# rev02_20.net
KiCad netlist of a schematic drawn in Altium Designer
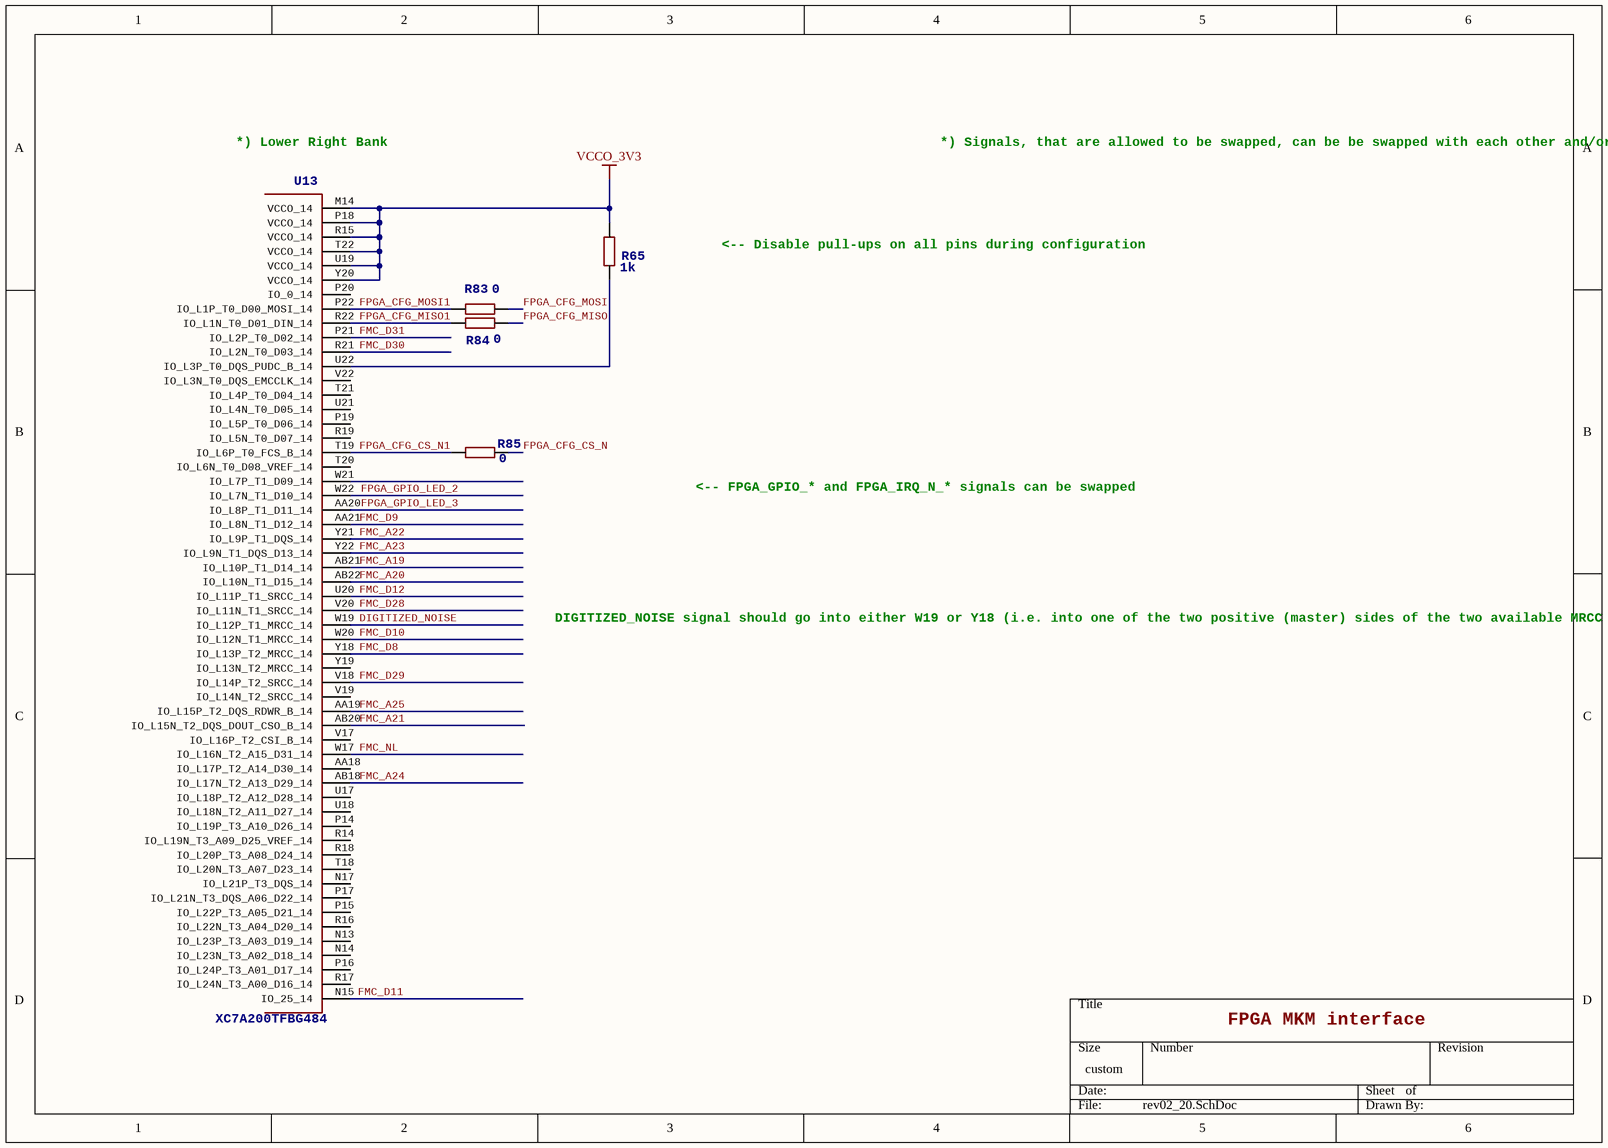
[diagram p0: rev02_20.SchDoc]

(export (version "E")
  (design (tool "Eeschema 10.0.6"))
  (components
    (comp (ref "R65")
      (value "1k")
      (footprint "R_0402")
      (description "0402 Resistor 5%")
      (fields (field (name "TOLERANCE") "5%") (field (name ">NAME") "R65"))
      (libsource (lib "resistor") (part "R-EU_R0402"))
    )
    (comp (ref "R83")
      (value "0")
      (footprint "R_0402")
      (description "0402 Resistor 5%")
      (libsource (lib "resistor") (part "R-EU_R0603"))
    )
    (comp (ref "R84")
      (value "0")
      (footprint "R_0402")
      (description "0402 Resistor 5%")
      (libsource (lib "resistor") (part "R-EU_R0603"))
    )
    (comp (ref "R85")
      (value "0")
      (footprint "R_0402")
      (description "0402 Resistor 5%")
      (libsource (lib "resistor") (part "R-EU_R0603"))
    )
    (comp (ref "U13")
      (value "XC7A200TFBG484")
      (footprint "BGA484C100P22X22_2300X2300X254")
      (description "Xilinx FPGA: XC7A200TFBG484")
      (fields
        (field (name "MFR") "Xilinx")
        (field (name "MPN") "XC7A200T-1FBG484C")
        (field (name ">NAME") "U13")
        (field (name ">VALUE") "XC7A200TFBG484")
      )
      (libsource (lib "Xilinx_XC7A200TFBG484") (part "XC7A200TFBG484"))
    )
  )
  (nets
    (net (code "1") (name "/DIGITIZED_NOISE") (class "Default")
      (node (ref "U13") (pin "W19") (pinfunction "IO_L12P_T1_MRCC_14_W19") (pintype "passive"))
    )
    (net (code "2") (name "/FMC_A19") (class "Default")
      (node (ref "U13") (pin "AB21") (pinfunction "IO_L10P_T1_D14_14_AB21") (pintype "passive"))
    )
    (net (code "3") (name "/FMC_A20") (class "Default")
      (node (ref "U13") (pin "AB22") (pinfunction "IO_L10N_T1_D15_14_AB22") (pintype "passive"))
    )
    (net (code "4") (name "/FMC_A21") (class "Default")
      (node (ref "U13") (pin "AB20") (pinfunction "IO_L15N_T2_DQS_DOUT_CSO_B_14_AB20") (pintype "passive"))
    )
    (net (code "5") (name "/FMC_A22") (class "Default")
      (node (ref "U13") (pin "Y21") (pinfunction "IO_L9P_T1_DQS_14_Y21") (pintype "passive"))
    )
    (net (code "6") (name "/FMC_A23") (class "Default")
      (node (ref "U13") (pin "Y22") (pinfunction "IO_L9N_T1_DQS_D13_14_Y22") (pintype "passive"))
    )
    (net (code "7") (name "/FMC_A24") (class "Default")
      (node (ref "U13") (pin "AB18") (pinfunction "IO_L17N_T2_A13_D29_14_AB18") (pintype "passive"))
    )
    (net (code "8") (name "/FMC_A25") (class "Default")
      (node (ref "U13") (pin "AA19") (pinfunction "IO_L15P_T2_DQS_RDWR_B_14_AA19") (pintype "passive"))
    )
    (net (code "9") (name "/FMC_D8") (class "Default")
      (node (ref "U13") (pin "Y18") (pinfunction "IO_L13P_T2_MRCC_14_Y18") (pintype "passive"))
    )
    (net (code "10") (name "/FMC_D9") (class "Default")
      (node (ref "U13") (pin "AA21") (pinfunction "IO_L8N_T1_D12_14_AA21") (pintype "passive"))
    )
    (net (code "11") (name "/FMC_D10") (class "Default")
      (node (ref "U13") (pin "W20") (pinfunction "IO_L12N_T1_MRCC_14_W20") (pintype "passive"))
    )
    (net (code "12") (name "/FMC_D11") (class "Default")
      (node (ref "U13") (pin "N15") (pinfunction "IO_25_14_N15") (pintype "passive"))
    )
    (net (code "13") (name "/FMC_D12") (class "Default")
      (node (ref "U13") (pin "U20") (pinfunction "IO_L11P_T1_SRCC_14_U20") (pintype "passive"))
    )
    (net (code "14") (name "/FMC_D28") (class "Default")
      (node (ref "U13") (pin "V20") (pinfunction "IO_L11N_T1_SRCC_14_V20") (pintype "passive"))
    )
    (net (code "15") (name "/FMC_D29") (class "Default")
      (node (ref "U13") (pin "V18") (pinfunction "IO_L14P_T2_SRCC_14_V18") (pintype "passive"))
    )
    (net (code "16") (name "/FMC_D30") (class "Default")
      (node (ref "U13") (pin "R21") (pinfunction "IO_L2N_T0_D03_14_R21") (pintype "passive"))
    )
    (net (code "17") (name "/FMC_D31") (class "Default")
      (node (ref "U13") (pin "P21") (pinfunction "IO_L2P_T0_D02_14_P21") (pintype "passive"))
    )
    (net (code "18") (name "/FMC_NL") (class "Default")
      (node (ref "U13") (pin "W17") (pinfunction "IO_L16N_T2_A15_D31_14_W17") (pintype "passive"))
    )
    (net (code "19") (name "/FPGA_CFG_CS_N") (class "Default")
      (node (ref "R85") (pin "1") (pinfunction "1_1") (pintype "passive"))
    )
    (net (code "20") (name "/FPGA_CFG_CS_N1") (class "Default")
      (node (ref "R85") (pin "2") (pinfunction "2_2") (pintype "passive"))
      (node (ref "U13") (pin "T19") (pinfunction "IO_L6P_T0_FCS_B_14_T19") (pintype "passive"))
    )
    (net (code "21") (name "/FPGA_CFG_MISO") (class "Default")
      (node (ref "R84") (pin "1") (pinfunction "1_1") (pintype "passive"))
    )
    (net (code "22") (name "/FPGA_CFG_MISO1") (class "Default")
      (node (ref "R84") (pin "2") (pinfunction "2_2") (pintype "passive"))
      (node (ref "U13") (pin "R22") (pinfunction "IO_L1N_T0_D01_DIN_14_R22") (pintype "passive"))
    )
    (net (code "23") (name "/FPGA_CFG_MOSI") (class "Default")
      (node (ref "R83") (pin "1") (pinfunction "1_1") (pintype "passive"))
    )
    (net (code "24") (name "/FPGA_CFG_MOSI1") (class "Default")
      (node (ref "R83") (pin "2") (pinfunction "2_2") (pintype "passive"))
      (node (ref "U13") (pin "P22") (pinfunction "IO_L1P_T0_D00_MOSI_14_P22") (pintype "passive"))
    )
    (net (code "25") (name "/FPGA_GPIO_LED_2") (class "Default")
      (node (ref "U13") (pin "W22") (pinfunction "IO_L7N_T1_D10_14_W22") (pintype "passive"))
    )
    (net (code "26") (name "/FPGA_GPIO_LED_3") (class "Default")
      (node (ref "U13") (pin "AA20") (pinfunction "IO_L8P_T1_D11_14_AA20") (pintype "passive"))
    )
    (net (code "27") (name "Net-(U13C-IO_L3P_T0_DQS_PUDC_B_14)") (class "Default")
      (node (ref "R65") (pin "1") (pinfunction "1_1") (pintype "passive"))
      (node (ref "U13") (pin "U22") (pinfunction "IO_L3P_T0_DQS_PUDC_B_14_U22") (pintype "passive"))
    )
    (net (code "28") (name "VCCO_3V3") (class "Default")
      (node (ref "R65") (pin "2") (pinfunction "2_2") (pintype "passive"))
      (node (ref "U13") (pin "M14") (pinfunction "VCCO_14_M14") (pintype "passive"))
      (node (ref "U13") (pin "P18") (pinfunction "VCCO_14_P18") (pintype "passive"))
      (node (ref "U13") (pin "R15") (pinfunction "VCCO_14_R15") (pintype "passive"))
      (node (ref "U13") (pin "T22") (pinfunction "VCCO_14_T22") (pintype "passive"))
      (node (ref "U13") (pin "U19") (pinfunction "VCCO_14_U19") (pintype "passive"))
      (node (ref "U13") (pin "Y20") (pinfunction "VCCO_14_Y20") (pintype "passive"))
    )
    (net (code "29") (name "unconnected-(U13C-IO_0_14-PadP20)") (class "Default")
      (node (ref "U13") (pin "P20") (pinfunction "IO_0_14_P20") (pintype "passive"))
    )
    (net (code "30") (name "unconnected-(U13C-IO_L3N_T0_DQS_EMCCLK_14-PadV22)") (class "Default")
      (node (ref "U13") (pin "V22") (pinfunction "IO_L3N_T0_DQS_EMCCLK_14_V22") (pintype "passive"))
    )
    (net (code "31") (name "unconnected-(U13C-IO_L4N_T0_D05_14-PadU21)") (class "Default")
      (node (ref "U13") (pin "U21") (pinfunction "IO_L4N_T0_D05_14_U21") (pintype "passive"))
    )
    (net (code "32") (name "unconnected-(U13C-IO_L4P_T0_D04_14-PadT21)") (class "Default")
      (node (ref "U13") (pin "T21") (pinfunction "IO_L4P_T0_D04_14_T21") (pintype "passive"))
    )
    (net (code "33") (name "unconnected-(U13C-IO_L5N_T0_D07_14-PadR19)") (class "Default")
      (node (ref "U13") (pin "R19") (pinfunction "IO_L5N_T0_D07_14_R19") (pintype "passive"))
    )
    (net (code "34") (name "unconnected-(U13C-IO_L5P_T0_D06_14-PadP19)") (class "Default")
      (node (ref "U13") (pin "P19") (pinfunction "IO_L5P_T0_D06_14_P19") (pintype "passive"))
    )
    (net (code "35") (name "unconnected-(U13C-IO_L6N_T0_D08_VREF_14-PadT20)") (class "Default")
      (node (ref "U13") (pin "T20") (pinfunction "IO_L6N_T0_D08_VREF_14_T20") (pintype "passive"))
    )
    (net (code "36") (name "unconnected-(U13C-IO_L7P_T1_D09_14-PadW21)") (class "Default")
      (node (ref "U13") (pin "W21") (pinfunction "IO_L7P_T1_D09_14_W21") (pintype "passive"))
    )
    (net (code "37") (name "unconnected-(U13C-IO_L13N_T2_MRCC_14-PadY19)") (class "Default")
      (node (ref "U13") (pin "Y19") (pinfunction "IO_L13N_T2_MRCC_14_Y19") (pintype "passive"))
    )
    (net (code "38") (name "unconnected-(U13C-IO_L14N_T2_SRCC_14-PadV19)") (class "Default")
      (node (ref "U13") (pin "V19") (pinfunction "IO_L14N_T2_SRCC_14_V19") (pintype "passive"))
    )
    (net (code "39") (name "unconnected-(U13C-IO_L16P_T2_CSI_B_14-PadV17)") (class "Default")
      (node (ref "U13") (pin "V17") (pinfunction "IO_L16P_T2_CSI_B_14_V17") (pintype "passive"))
    )
    (net (code "40") (name "unconnected-(U13C-IO_L17P_T2_A14_D30_14-PadAA18)") (class "Default")
      (node (ref "U13") (pin "AA18") (pinfunction "IO_L17P_T2_A14_D30_14_AA18") (pintype "passive"))
    )
    (net (code "41") (name "unconnected-(U13C-IO_L18N_T2_A11_D27_14-PadU18)") (class "Default")
      (node (ref "U13") (pin "U18") (pinfunction "IO_L18N_T2_A11_D27_14_U18") (pintype "passive"))
    )
    (net (code "42") (name "unconnected-(U13C-IO_L18P_T2_A12_D28_14-PadU17)") (class "Default")
      (node (ref "U13") (pin "U17") (pinfunction "IO_L18P_T2_A12_D28_14_U17") (pintype "passive"))
    )
    (net (code "43") (name "unconnected-(U13C-IO_L19N_T3_A09_D25_VREF_14-PadR14)") (class "Default")
      (node (ref "U13") (pin "R14") (pinfunction "IO_L19N_T3_A09_D25_VREF_14_R14") (pintype "passive"))
    )
    (net (code "44") (name "unconnected-(U13C-IO_L19P_T3_A10_D26_14-PadP14)") (class "Default")
      (node (ref "U13") (pin "P14") (pinfunction "IO_L19P_T3_A10_D26_14_P14") (pintype "passive"))
    )
    (net (code "45") (name "unconnected-(U13C-IO_L20N_T3_A07_D23_14-PadT18)") (class "Default")
      (node (ref "U13") (pin "T18") (pinfunction "IO_L20N_T3_A07_D23_14_T18") (pintype "passive"))
    )
    (net (code "46") (name "unconnected-(U13C-IO_L20P_T3_A08_D24_14-PadR18)") (class "Default")
      (node (ref "U13") (pin "R18") (pinfunction "IO_L20P_T3_A08_D24_14_R18") (pintype "passive"))
    )
    (net (code "47") (name "unconnected-(U13C-IO_L21N_T3_DQS_A06_D22_14-PadP17)") (class "Default")
      (node (ref "U13") (pin "P17") (pinfunction "IO_L21N_T3_DQS_A06_D22_14_P17") (pintype "passive"))
    )
    (net (code "48") (name "unconnected-(U13C-IO_L21P_T3_DQS_14-PadN17)") (class "Default")
      (node (ref "U13") (pin "N17") (pinfunction "IO_L21P_T3_DQS_14_N17") (pintype "passive"))
    )
    (net (code "49") (name "unconnected-(U13C-IO_L22N_T3_A04_D20_14-PadR16)") (class "Default")
      (node (ref "U13") (pin "R16") (pinfunction "IO_L22N_T3_A04_D20_14_R16") (pintype "passive"))
    )
    (net (code "50") (name "unconnected-(U13C-IO_L22P_T3_A05_D21_14-PadP15)") (class "Default")
      (node (ref "U13") (pin "P15") (pinfunction "IO_L22P_T3_A05_D21_14_P15") (pintype "passive"))
    )
    (net (code "51") (name "unconnected-(U13C-IO_L23N_T3_A02_D18_14-PadN14)") (class "Default")
      (node (ref "U13") (pin "N14") (pinfunction "IO_L23N_T3_A02_D18_14_N14") (pintype "passive"))
    )
    (net (code "52") (name "unconnected-(U13C-IO_L23P_T3_A03_D19_14-PadN13)") (class "Default")
      (node (ref "U13") (pin "N13") (pinfunction "IO_L23P_T3_A03_D19_14_N13") (pintype "passive"))
    )
    (net (code "53") (name "unconnected-(U13C-IO_L24N_T3_A00_D16_14-PadR17)") (class "Default")
      (node (ref "U13") (pin "R17") (pinfunction "IO_L24N_T3_A00_D16_14_R17") (pintype "passive"))
    )
    (net (code "54") (name "unconnected-(U13C-IO_L24P_T3_A01_D17_14-PadP16)") (class "Default")
      (node (ref "U13") (pin "P16") (pinfunction "IO_L24P_T3_A01_D17_14_P16") (pintype "passive"))
    )
  )
)
